# fCPU.net
KiCad netlist of a schematic drawn in EAGLE
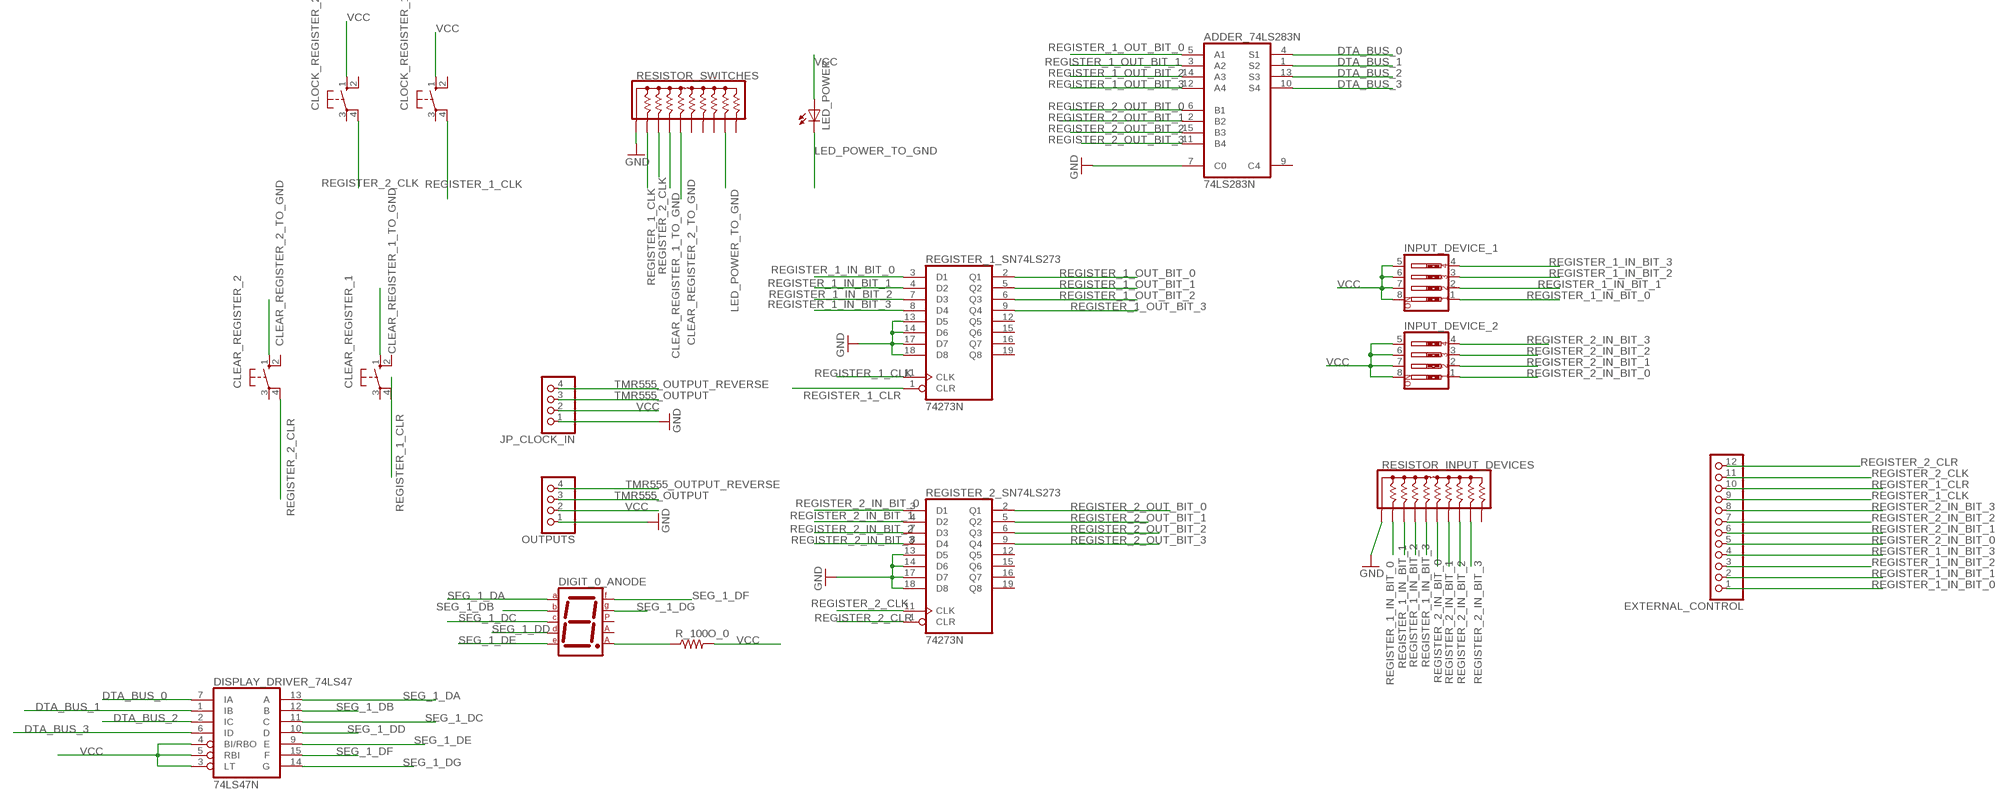
[diagram p0: schematic, sheet 1]

(export (version "E")
  (design (tool "Eeschema 10.0.6"))
  (components
    (comp (ref "ADDER_74LS283N")
      (value "74LS283N")
      (footprint "eagle-import:DIL16")
      (libsource (lib "eagle-import") (part "74283NLS"))
    )
    (comp (ref "CLEAR_REGISTER_1")
      (value "10-XX")
      (footprint "eagle-import:B3F-10XX")
      (fields (field (name "MPN") "B3F-1000"))
      (libsource (lib "eagle-import") (part "10-XX"))
    )
    (comp (ref "CLEAR_REGISTER_2")
      (value "10-XX")
      (footprint "eagle-import:B3F-10XX")
      (fields (field (name "MPN") "B3F-1000"))
      (libsource (lib "eagle-import") (part "10-XX"))
    )
    (comp (ref "CLOCK_REGISTER_1")
      (value "10-XX")
      (footprint "eagle-import:B3F-10XX")
      (fields (field (name "MPN") "B3F-1000"))
      (libsource (lib "eagle-import") (part "10-XX"))
    )
    (comp (ref "CLOCK_REGISTER_2")
      (value "10-XX")
      (footprint "eagle-import:B3F-10XX")
      (fields (field (name "MPN") "B3F-1000"))
      (libsource (lib "eagle-import") (part "10-XX"))
    )
    (comp (ref "DIGIT_0_ANODE")
      (value "7SEG-CA")
      (footprint "eagle-import:7SEG-13")
      (libsource (lib "eagle-import") (part "7SEG-CA"))
    )
    (comp (ref "DISPLAY_DRIVER_74LS47")
      (value "74LS47N")
      (footprint "eagle-import:DIL16")
      (libsource (lib "eagle-import") (part "7447NLS"))
    )
    (comp (ref "EXTERNAL_CONTROL")
      (value "PINHD-1X12")
      (footprint "eagle-import:1X12")
      (libsource (lib "eagle-import") (part "PINHD-1X12"))
    )
    (comp (ref "INPUT_DEVICE_1")
      (value "SW_DIP-4")
      (footprint "eagle-import:EDG-04")
      (libsource (lib "eagle-import") (part "SW_DIP-4"))
    )
    (comp (ref "INPUT_DEVICE_2")
      (value "SW_DIP-4")
      (footprint "eagle-import:EDG-04")
      (libsource (lib "eagle-import") (part "SW_DIP-4"))
    )
    (comp (ref "JP_CLOCK_IN")
      (value "PINHD-1X4")
      (footprint "eagle-import:1X04")
      (libsource (lib "eagle-import") (part "PINHD-1X4"))
    )
    (comp (ref "LED_POWER")
      (value "LEDSMT1206")
      (footprint "eagle-import:1206")
      (libsource (lib "eagle-import") (part "LEDSMT1206"))
    )
    (comp (ref "OUTPUTS")
      (value "PINHD-1X4")
      (footprint "eagle-import:1X04")
      (libsource (lib "eagle-import") (part "PINHD-1X4"))
    )
    (comp (ref "REGISTER_1_SN74LS273")
      (value "74273N")
      (footprint "eagle-import:DIL20")
      (libsource (lib "eagle-import") (part "74273N"))
    )
    (comp (ref "REGISTER_2_SN74LS273")
      (value "74273N")
      (footprint "eagle-import:DIL20")
      (libsource (lib "eagle-import") (part "74273N"))
    )
    (comp (ref "RESISTOR_INPUT_DEVICES")
      (value "4610X")
      (footprint "eagle-import:SIP10")
      (libsource (lib "eagle-import") (part "4610X"))
    )
    (comp (ref "RESISTOR_SWITCHES")
      (value "4610X")
      (footprint "eagle-import:SIP10")
      (libsource (lib "eagle-import") (part "4610X"))
    )
    (comp (ref "R_100O_0")
      (value "R-US_R1206")
      (footprint "eagle-import:R1206")
      (libsource (lib "eagle-import") (part "R-US_R1206"))
    )
  )
  (nets
    (net (code "1") (name "/CLEAR_REGISTER_1_TO_GND") (class "Default")
      (node (ref "CLEAR_REGISTER_1") (pin "1") (pinfunction "S_1") (pintype "passive"))
      (node (ref "RESISTOR_SWITCHES") (pin "4") (pinfunction "4_4") (pintype "passive"))
    )
    (net (code "2") (name "/CLEAR_REGISTER_2_TO_GND") (class "Default")
      (node (ref "CLEAR_REGISTER_2") (pin "1") (pinfunction "S_1") (pintype "passive"))
      (node (ref "RESISTOR_SWITCHES") (pin "5") (pinfunction "5_5") (pintype "passive"))
    )
    (net (code "3") (name "/DTA_BUS_0") (class "Default")
      (node (ref "ADDER_74LS283N") (pin "4") (pinfunction "S1_4") (pintype "output"))
      (node (ref "DISPLAY_DRIVER_74LS47") (pin "7") (pinfunction "IA_7") (pintype "input"))
    )
    (net (code "4") (name "/DTA_BUS_1") (class "Default")
      (node (ref "ADDER_74LS283N") (pin "1") (pinfunction "S2_1") (pintype "output"))
      (node (ref "DISPLAY_DRIVER_74LS47") (pin "1") (pinfunction "IB_1") (pintype "input"))
    )
    (net (code "5") (name "/DTA_BUS_2") (class "Default")
      (node (ref "ADDER_74LS283N") (pin "13") (pinfunction "S3_13") (pintype "output"))
      (node (ref "DISPLAY_DRIVER_74LS47") (pin "2") (pinfunction "IC_2") (pintype "input"))
    )
    (net (code "6") (name "/DTA_BUS_3") (class "Default")
      (node (ref "ADDER_74LS283N") (pin "10") (pinfunction "S4_10") (pintype "output"))
      (node (ref "DISPLAY_DRIVER_74LS47") (pin "6") (pinfunction "ID_6") (pintype "input"))
    )
    (net (code "7") (name "/LED_POWER_TO_GND") (class "Default")
      (node (ref "LED_POWER") (pin "C") (pinfunction "C_C") (pintype "passive"))
      (node (ref "RESISTOR_SWITCHES") (pin "9") (pinfunction "9_9") (pintype "passive"))
    )
    (net (code "8") (name "/REGISTER_1_CLK") (class "Default")
      (node (ref "CLOCK_REGISTER_1") (pin "4") (pinfunction "P1_4") (pintype "passive"))
      (node (ref "EXTERNAL_CONTROL") (pin "9") (pinfunction "9_9") (pintype "passive"))
      (node (ref "REGISTER_1_SN74LS273") (pin "11") (pinfunction "CLK_11") (pintype "input"))
      (node (ref "RESISTOR_SWITCHES") (pin "2") (pinfunction "2_2") (pintype "passive"))
    )
    (net (code "9") (name "/REGISTER_1_CLR") (class "Default")
      (node (ref "CLEAR_REGISTER_1") (pin "4") (pinfunction "P1_4") (pintype "passive"))
      (node (ref "EXTERNAL_CONTROL") (pin "10") (pinfunction "10_10") (pintype "passive"))
      (node (ref "REGISTER_1_SN74LS273") (pin "1") (pinfunction "CLR_1") (pintype "input"))
    )
    (net (code "10") (name "/REGISTER_1_IN_BIT_0") (class "Default")
      (node (ref "EXTERNAL_CONTROL") (pin "1") (pinfunction "1_1") (pintype "passive"))
      (node (ref "INPUT_DEVICE_1") (pin "1") (pinfunction "1_1") (pintype "passive"))
      (node (ref "REGISTER_1_SN74LS273") (pin "3") (pinfunction "D1_3") (pintype "input"))
      (node (ref "RESISTOR_INPUT_DEVICES") (pin "2") (pinfunction "2_2") (pintype "passive"))
    )
    (net (code "11") (name "/REGISTER_1_IN_BIT_1") (class "Default")
      (node (ref "EXTERNAL_CONTROL") (pin "2") (pinfunction "2_2") (pintype "passive"))
      (node (ref "INPUT_DEVICE_1") (pin "2") (pinfunction "2_2") (pintype "passive"))
      (node (ref "REGISTER_1_SN74LS273") (pin "4") (pinfunction "D2_4") (pintype "input"))
      (node (ref "RESISTOR_INPUT_DEVICES") (pin "3") (pinfunction "3_3") (pintype "passive"))
    )
    (net (code "12") (name "/REGISTER_1_IN_BIT_2") (class "Default")
      (node (ref "EXTERNAL_CONTROL") (pin "3") (pinfunction "3_3") (pintype "passive"))
      (node (ref "INPUT_DEVICE_1") (pin "3") (pinfunction "3_3") (pintype "passive"))
      (node (ref "REGISTER_1_SN74LS273") (pin "7") (pinfunction "D3_7") (pintype "input"))
      (node (ref "RESISTOR_INPUT_DEVICES") (pin "4") (pinfunction "4_4") (pintype "passive"))
    )
    (net (code "13") (name "/REGISTER_1_IN_BIT_3") (class "Default")
      (node (ref "EXTERNAL_CONTROL") (pin "4") (pinfunction "4_4") (pintype "passive"))
      (node (ref "INPUT_DEVICE_1") (pin "4") (pinfunction "4_4") (pintype "passive"))
      (node (ref "REGISTER_1_SN74LS273") (pin "8") (pinfunction "D4_8") (pintype "input"))
      (node (ref "RESISTOR_INPUT_DEVICES") (pin "5") (pinfunction "5_5") (pintype "passive"))
    )
    (net (code "14") (name "/REGISTER_1_OUT_BIT_0") (class "Default")
      (node (ref "ADDER_74LS283N") (pin "5") (pinfunction "A1_5") (pintype "input"))
      (node (ref "REGISTER_1_SN74LS273") (pin "2") (pinfunction "Q1_2") (pintype "output"))
    )
    (net (code "15") (name "/REGISTER_1_OUT_BIT_1") (class "Default")
      (node (ref "ADDER_74LS283N") (pin "3") (pinfunction "A2_3") (pintype "input"))
      (node (ref "REGISTER_1_SN74LS273") (pin "5") (pinfunction "Q2_5") (pintype "output"))
    )
    (net (code "16") (name "/REGISTER_1_OUT_BIT_2") (class "Default")
      (node (ref "ADDER_74LS283N") (pin "14") (pinfunction "A3_14") (pintype "input"))
      (node (ref "REGISTER_1_SN74LS273") (pin "6") (pinfunction "Q3_6") (pintype "output"))
    )
    (net (code "17") (name "/REGISTER_1_OUT_BIT_3") (class "Default")
      (node (ref "ADDER_74LS283N") (pin "12") (pinfunction "A4_12") (pintype "input"))
      (node (ref "REGISTER_1_SN74LS273") (pin "9") (pinfunction "Q4_9") (pintype "output"))
    )
    (net (code "18") (name "/REGISTER_2_CLK") (class "Default")
      (node (ref "CLOCK_REGISTER_2") (pin "4") (pinfunction "P1_4") (pintype "passive"))
      (node (ref "EXTERNAL_CONTROL") (pin "11") (pinfunction "11_11") (pintype "passive"))
      (node (ref "REGISTER_2_SN74LS273") (pin "11") (pinfunction "CLK_11") (pintype "input"))
      (node (ref "RESISTOR_SWITCHES") (pin "3") (pinfunction "3_3") (pintype "passive"))
    )
    (net (code "19") (name "/REGISTER_2_CLR") (class "Default")
      (node (ref "CLEAR_REGISTER_2") (pin "4") (pinfunction "P1_4") (pintype "passive"))
      (node (ref "EXTERNAL_CONTROL") (pin "12") (pinfunction "12_12") (pintype "passive"))
      (node (ref "REGISTER_2_SN74LS273") (pin "1") (pinfunction "CLR_1") (pintype "input"))
    )
    (net (code "20") (name "/REGISTER_2_IN_BIT_0") (class "Default")
      (node (ref "EXTERNAL_CONTROL") (pin "5") (pinfunction "5_5") (pintype "passive"))
      (node (ref "INPUT_DEVICE_2") (pin "1") (pinfunction "1_1") (pintype "passive"))
      (node (ref "REGISTER_2_SN74LS273") (pin "3") (pinfunction "D1_3") (pintype "input"))
      (node (ref "RESISTOR_INPUT_DEVICES") (pin "6") (pinfunction "6_6") (pintype "passive"))
    )
    (net (code "21") (name "/REGISTER_2_IN_BIT_1") (class "Default")
      (node (ref "EXTERNAL_CONTROL") (pin "6") (pinfunction "6_6") (pintype "passive"))
      (node (ref "INPUT_DEVICE_2") (pin "2") (pinfunction "2_2") (pintype "passive"))
      (node (ref "REGISTER_2_SN74LS273") (pin "4") (pinfunction "D2_4") (pintype "input"))
      (node (ref "RESISTOR_INPUT_DEVICES") (pin "7") (pinfunction "7_7") (pintype "passive"))
    )
    (net (code "22") (name "/REGISTER_2_IN_BIT_2") (class "Default")
      (node (ref "EXTERNAL_CONTROL") (pin "7") (pinfunction "7_7") (pintype "passive"))
      (node (ref "INPUT_DEVICE_2") (pin "3") (pinfunction "3_3") (pintype "passive"))
      (node (ref "REGISTER_2_SN74LS273") (pin "7") (pinfunction "D3_7") (pintype "input"))
      (node (ref "RESISTOR_INPUT_DEVICES") (pin "8") (pinfunction "8_8") (pintype "passive"))
    )
    (net (code "23") (name "/REGISTER_2_IN_BIT_3") (class "Default")
      (node (ref "EXTERNAL_CONTROL") (pin "8") (pinfunction "8_8") (pintype "passive"))
      (node (ref "INPUT_DEVICE_2") (pin "4") (pinfunction "4_4") (pintype "passive"))
      (node (ref "REGISTER_2_SN74LS273") (pin "8") (pinfunction "D4_8") (pintype "input"))
      (node (ref "RESISTOR_INPUT_DEVICES") (pin "9") (pinfunction "9_9") (pintype "passive"))
    )
    (net (code "24") (name "/REGISTER_2_OUT_BIT_0") (class "Default")
      (node (ref "ADDER_74LS283N") (pin "6") (pinfunction "B1_6") (pintype "input"))
      (node (ref "REGISTER_2_SN74LS273") (pin "2") (pinfunction "Q1_2") (pintype "output"))
    )
    (net (code "25") (name "/REGISTER_2_OUT_BIT_1") (class "Default")
      (node (ref "ADDER_74LS283N") (pin "2") (pinfunction "B2_2") (pintype "input"))
      (node (ref "REGISTER_2_SN74LS273") (pin "5") (pinfunction "Q2_5") (pintype "output"))
    )
    (net (code "26") (name "/REGISTER_2_OUT_BIT_2") (class "Default")
      (node (ref "ADDER_74LS283N") (pin "15") (pinfunction "B3_15") (pintype "input"))
      (node (ref "REGISTER_2_SN74LS273") (pin "6") (pinfunction "Q3_6") (pintype "output"))
    )
    (net (code "27") (name "/REGISTER_2_OUT_BIT_3") (class "Default")
      (node (ref "ADDER_74LS283N") (pin "11") (pinfunction "B4_11") (pintype "input"))
      (node (ref "REGISTER_2_SN74LS273") (pin "9") (pinfunction "Q4_9") (pintype "output"))
    )
    (net (code "28") (name "/SEG_1_DA") (class "Default")
      (node (ref "DIGIT_0_ANODE") (pin "7") (pinfunction "A_7") (pintype "passive"))
      (node (ref "DISPLAY_DRIVER_74LS47") (pin "13") (pinfunction "A_13") (pintype "output"))
    )
    (net (code "29") (name "/SEG_1_DB") (class "Default")
      (node (ref "DIGIT_0_ANODE") (pin "6") (pinfunction "B_6") (pintype "passive"))
      (node (ref "DISPLAY_DRIVER_74LS47") (pin "12") (pinfunction "B_12") (pintype "output"))
    )
    (net (code "30") (name "/SEG_1_DC") (class "Default")
      (node (ref "DIGIT_0_ANODE") (pin "4") (pinfunction "C_4") (pintype "passive"))
      (node (ref "DISPLAY_DRIVER_74LS47") (pin "11") (pinfunction "C_11") (pintype "output"))
    )
    (net (code "31") (name "/SEG_1_DD") (class "Default")
      (node (ref "DIGIT_0_ANODE") (pin "2") (pinfunction "D_2") (pintype "passive"))
      (node (ref "DISPLAY_DRIVER_74LS47") (pin "10") (pinfunction "D_10") (pintype "output"))
    )
    (net (code "32") (name "/SEG_1_DE") (class "Default")
      (node (ref "DIGIT_0_ANODE") (pin "1") (pinfunction "E_1") (pintype "passive"))
      (node (ref "DISPLAY_DRIVER_74LS47") (pin "9") (pinfunction "E_9") (pintype "output"))
    )
    (net (code "33") (name "/SEG_1_DF") (class "Default")
      (node (ref "DIGIT_0_ANODE") (pin "9") (pinfunction "F_9") (pintype "passive"))
      (node (ref "DISPLAY_DRIVER_74LS47") (pin "15") (pinfunction "F_15") (pintype "output"))
    )
    (net (code "34") (name "/SEG_1_DG") (class "Default")
      (node (ref "DIGIT_0_ANODE") (pin "10") (pinfunction "G_10") (pintype "passive"))
      (node (ref "DISPLAY_DRIVER_74LS47") (pin "14") (pinfunction "G_14") (pintype "output"))
    )
    (net (code "35") (name "/TMR555_OUTPUT") (class "Default")
      (node (ref "JP_CLOCK_IN") (pin "3") (pinfunction "3_3") (pintype "passive"))
      (node (ref "OUTPUTS") (pin "3") (pinfunction "3_3") (pintype "passive"))
    )
    (net (code "36") (name "/TMR555_OUTPUT_REVERSE") (class "Default")
      (node (ref "JP_CLOCK_IN") (pin "4") (pinfunction "4_4") (pintype "passive"))
      (node (ref "OUTPUTS") (pin "4") (pinfunction "4_4") (pintype "passive"))
    )
    (net (code "37") (name "/VCC") (class "Default")
      (node (ref "CLOCK_REGISTER_1") (pin "1") (pinfunction "S_1") (pintype "passive"))
      (node (ref "CLOCK_REGISTER_2") (pin "1") (pinfunction "S_1") (pintype "passive"))
      (node (ref "DISPLAY_DRIVER_74LS47") (pin "3") (pinfunction "LT_3") (pintype "input"))
      (node (ref "DISPLAY_DRIVER_74LS47") (pin "4") (pinfunction "BI/RBO_4") (pintype "input"))
      (node (ref "DISPLAY_DRIVER_74LS47") (pin "5") (pinfunction "RBI_5") (pintype "input"))
      (node (ref "INPUT_DEVICE_1") (pin "5") (pinfunction "5_5") (pintype "passive"))
      (node (ref "INPUT_DEVICE_1") (pin "6") (pinfunction "6_6") (pintype "passive"))
      (node (ref "INPUT_DEVICE_1") (pin "7") (pinfunction "7_7") (pintype "passive"))
      (node (ref "INPUT_DEVICE_1") (pin "8") (pinfunction "8_8") (pintype "passive"))
      (node (ref "INPUT_DEVICE_2") (pin "5") (pinfunction "5_5") (pintype "passive"))
      (node (ref "INPUT_DEVICE_2") (pin "6") (pinfunction "6_6") (pintype "passive"))
      (node (ref "INPUT_DEVICE_2") (pin "7") (pinfunction "7_7") (pintype "passive"))
      (node (ref "INPUT_DEVICE_2") (pin "8") (pinfunction "8_8") (pintype "passive"))
      (node (ref "JP_CLOCK_IN") (pin "2") (pinfunction "2_2") (pintype "passive"))
      (node (ref "LED_POWER") (pin "A") (pinfunction "A_A") (pintype "passive"))
      (node (ref "OUTPUTS") (pin "2") (pinfunction "2_2") (pintype "passive"))
      (node (ref "R_100O_0") (pin "2") (pinfunction "2_2") (pintype "passive"))
    )
    (net (code "38") (name "GND") (class "Default")
      (node (ref "ADDER_74LS283N") (pin "7") (pinfunction "C0_7") (pintype "input"))
      (node (ref "JP_CLOCK_IN") (pin "1") (pinfunction "1_1") (pintype "passive"))
      (node (ref "OUTPUTS") (pin "1") (pinfunction "1_1") (pintype "passive"))
      (node (ref "REGISTER_1_SN74LS273") (pin "13") (pinfunction "D5_13") (pintype "input"))
      (node (ref "REGISTER_1_SN74LS273") (pin "14") (pinfunction "D6_14") (pintype "input"))
      (node (ref "REGISTER_1_SN74LS273") (pin "17") (pinfunction "D7_17") (pintype "input"))
      (node (ref "REGISTER_1_SN74LS273") (pin "18") (pinfunction "D8_18") (pintype "input"))
      (node (ref "REGISTER_2_SN74LS273") (pin "13") (pinfunction "D5_13") (pintype "input"))
      (node (ref "REGISTER_2_SN74LS273") (pin "14") (pinfunction "D6_14") (pintype "input"))
      (node (ref "REGISTER_2_SN74LS273") (pin "17") (pinfunction "D7_17") (pintype "input"))
      (node (ref "REGISTER_2_SN74LS273") (pin "18") (pinfunction "D8_18") (pintype "input"))
      (node (ref "RESISTOR_INPUT_DEVICES") (pin "1") (pinfunction "1_1") (pintype "passive"))
      (node (ref "RESISTOR_SWITCHES") (pin "1") (pinfunction "1_1") (pintype "passive"))
    )
    (net (code "39") (name "Net-(DIGIT_0_ANODE-CA2)") (class "Default")
      (node (ref "DIGIT_0_ANODE") (pin "8") (pinfunction "CA2_8") (pintype "passive"))
      (node (ref "R_100O_0") (pin "1") (pinfunction "1_1") (pintype "passive"))
    )
    (net (code "40") (name "unconnected-(ADDER_74LS283NA-C4-Pad9)") (class "Default")
      (node (ref "ADDER_74LS283N") (pin "9") (pinfunction "C4_9") (pintype "output"))
    )
    (net (code "41") (name "unconnected-(CLEAR_REGISTER_1-P-Pad3)") (class "Default")
      (node (ref "CLEAR_REGISTER_1") (pin "3") (pinfunction "P_3") (pintype "passive"))
    )
    (net (code "42") (name "unconnected-(CLEAR_REGISTER_1-S1-Pad2)") (class "Default")
      (node (ref "CLEAR_REGISTER_1") (pin "2") (pinfunction "S1_2") (pintype "passive"))
    )
    (net (code "43") (name "unconnected-(CLEAR_REGISTER_2-P-Pad3)") (class "Default")
      (node (ref "CLEAR_REGISTER_2") (pin "3") (pinfunction "P_3") (pintype "passive"))
    )
    (net (code "44") (name "unconnected-(CLEAR_REGISTER_2-S1-Pad2)") (class "Default")
      (node (ref "CLEAR_REGISTER_2") (pin "2") (pinfunction "S1_2") (pintype "passive"))
    )
    (net (code "45") (name "unconnected-(CLOCK_REGISTER_1-P-Pad3)") (class "Default")
      (node (ref "CLOCK_REGISTER_1") (pin "3") (pinfunction "P_3") (pintype "passive"))
    )
    (net (code "46") (name "unconnected-(CLOCK_REGISTER_1-S1-Pad2)") (class "Default")
      (node (ref "CLOCK_REGISTER_1") (pin "2") (pinfunction "S1_2") (pintype "passive"))
    )
    (net (code "47") (name "unconnected-(CLOCK_REGISTER_2-P-Pad3)") (class "Default")
      (node (ref "CLOCK_REGISTER_2") (pin "3") (pinfunction "P_3") (pintype "passive"))
    )
    (net (code "48") (name "unconnected-(CLOCK_REGISTER_2-S1-Pad2)") (class "Default")
      (node (ref "CLOCK_REGISTER_2") (pin "2") (pinfunction "S1_2") (pintype "passive"))
    )
    (net (code "49") (name "unconnected-(DIGIT_0_ANODE-CA1-Pad3)") (class "Default")
      (node (ref "DIGIT_0_ANODE") (pin "3") (pinfunction "CA1_3") (pintype "passive"))
    )
    (net (code "50") (name "unconnected-(DIGIT_0_ANODE-DP-Pad5)") (class "Default")
      (node (ref "DIGIT_0_ANODE") (pin "5") (pinfunction "DP_5") (pintype "passive"))
    )
    (net (code "51") (name "unconnected-(REGISTER_1_SN74LS273A-Q5-Pad12)") (class "Default")
      (node (ref "REGISTER_1_SN74LS273") (pin "12") (pinfunction "Q5_12") (pintype "output"))
    )
    (net (code "52") (name "unconnected-(REGISTER_1_SN74LS273A-Q6-Pad15)") (class "Default")
      (node (ref "REGISTER_1_SN74LS273") (pin "15") (pinfunction "Q6_15") (pintype "output"))
    )
    (net (code "53") (name "unconnected-(REGISTER_1_SN74LS273A-Q7-Pad16)") (class "Default")
      (node (ref "REGISTER_1_SN74LS273") (pin "16") (pinfunction "Q7_16") (pintype "output"))
    )
    (net (code "54") (name "unconnected-(REGISTER_1_SN74LS273A-Q8-Pad19)") (class "Default")
      (node (ref "REGISTER_1_SN74LS273") (pin "19") (pinfunction "Q8_19") (pintype "output"))
    )
    (net (code "55") (name "unconnected-(REGISTER_2_SN74LS273A-Q5-Pad12)") (class "Default")
      (node (ref "REGISTER_2_SN74LS273") (pin "12") (pinfunction "Q5_12") (pintype "output"))
    )
    (net (code "56") (name "unconnected-(REGISTER_2_SN74LS273A-Q6-Pad15)") (class "Default")
      (node (ref "REGISTER_2_SN74LS273") (pin "15") (pinfunction "Q6_15") (pintype "output"))
    )
    (net (code "57") (name "unconnected-(REGISTER_2_SN74LS273A-Q7-Pad16)") (class "Default")
      (node (ref "REGISTER_2_SN74LS273") (pin "16") (pinfunction "Q7_16") (pintype "output"))
    )
    (net (code "58") (name "unconnected-(REGISTER_2_SN74LS273A-Q8-Pad19)") (class "Default")
      (node (ref "REGISTER_2_SN74LS273") (pin "19") (pinfunction "Q8_19") (pintype "output"))
    )
    (net (code "59") (name "unconnected-(RESISTOR_INPUT_DEVICES-Pad10)") (class "Default")
      (node (ref "RESISTOR_INPUT_DEVICES") (pin "10") (pinfunction "10_10") (pintype "passive"))
    )
    (net (code "60") (name "unconnected-(RESISTOR_SWITCHES-Pad6)") (class "Default")
      (node (ref "RESISTOR_SWITCHES") (pin "6") (pinfunction "6_6") (pintype "passive"))
    )
    (net (code "61") (name "unconnected-(RESISTOR_SWITCHES-Pad7)") (class "Default")
      (node (ref "RESISTOR_SWITCHES") (pin "7") (pinfunction "7_7") (pintype "passive"))
    )
    (net (code "62") (name "unconnected-(RESISTOR_SWITCHES-Pad8)") (class "Default")
      (node (ref "RESISTOR_SWITCHES") (pin "8") (pinfunction "8_8") (pintype "passive"))
    )
    (net (code "63") (name "unconnected-(RESISTOR_SWITCHES-Pad10)") (class "Default")
      (node (ref "RESISTOR_SWITCHES") (pin "10") (pinfunction "10_10") (pintype "passive"))
    )
  )
)
